# 03_Beam_Inputs.net
KiCad netlist of a schematic drawn in Altium Designer
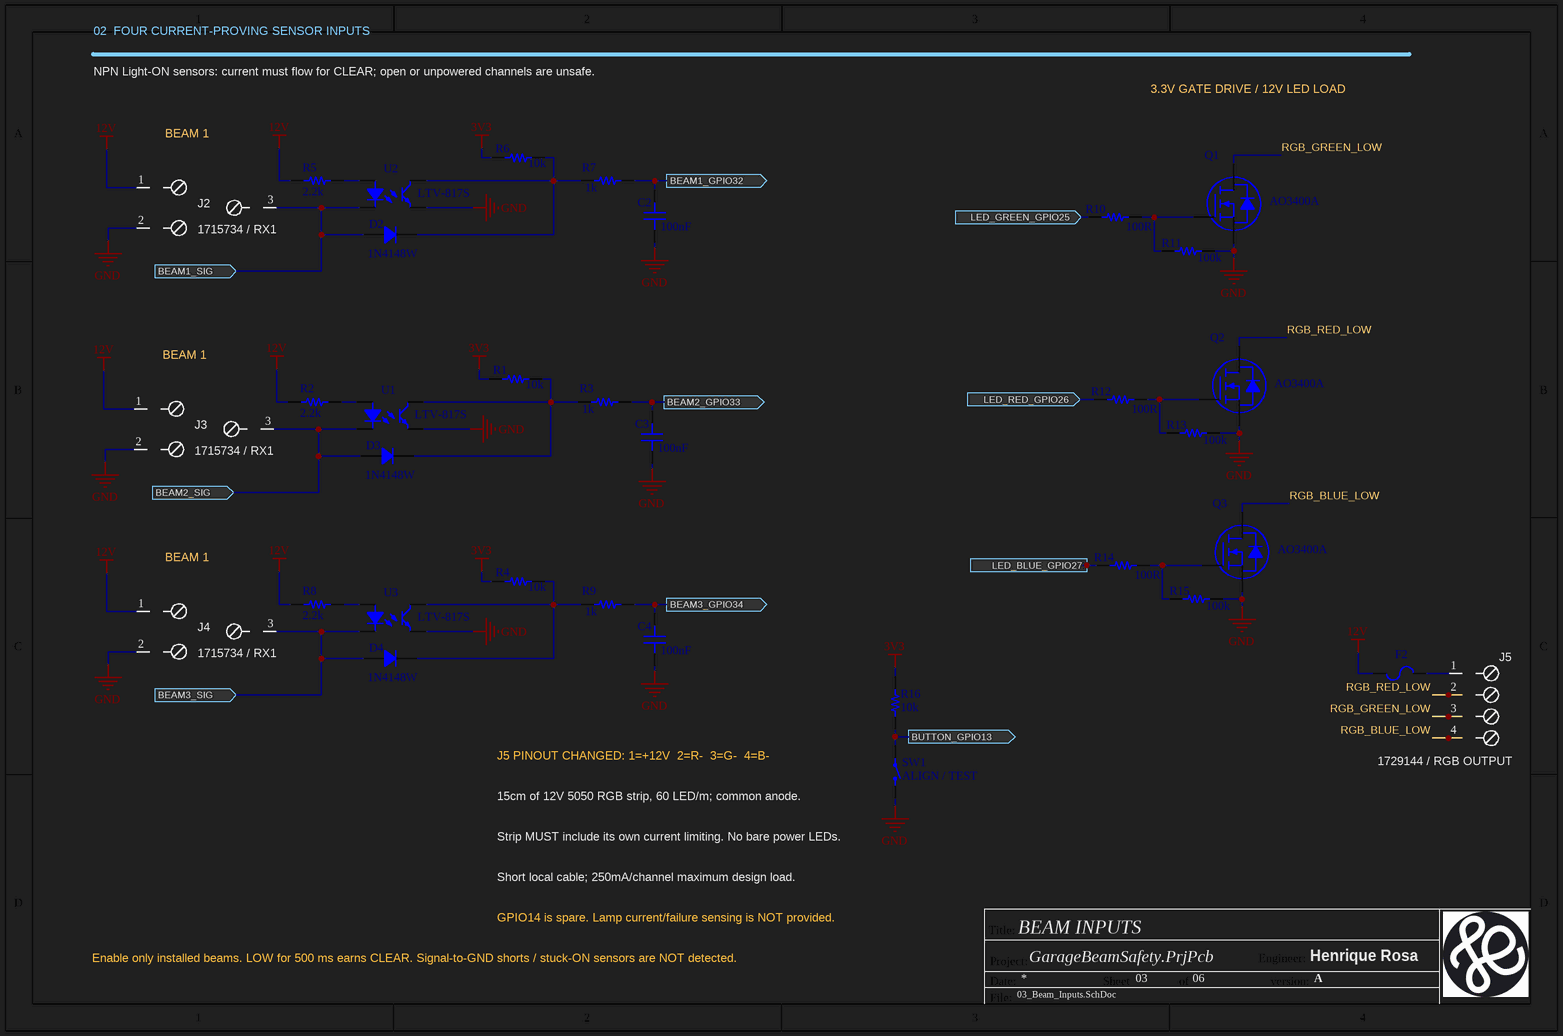
[diagram p0: 03_Beam_Inputs.SchDoc]

(export (version "E")
  (design (tool "Eeschema 10.0.6"))
  (components
    (comp (ref "C2")
      (value "100nF")
      (footprint "PCB - CAPACITOR - MLCC - MURATA GRM21B 0805_2012:MURATA GRM21B 0805_2012")
      (description "SMT Capacitor")
      (fields (field (name "PART NUMBER") "GRM21BR71H104KA01L") (field (name "MANUFACTURER") "Murata"))
      (libsource (lib "SCH - PASSIVES - CAPACITOR") (part "Capacitor"))
    )
    (comp (ref "C3")
      (value "100nF")
      (footprint "PCB - CAPACITOR - MLCC - MURATA GRM21B 0805_2012:MURATA GRM21B 0805_2012")
      (description "SMT Capacitor")
      (fields (field (name "PART NUMBER") "GRM21BR71H104KA01L") (field (name "MANUFACTURER") "Murata"))
      (libsource (lib "SCH - PASSIVES - CAPACITOR") (part "Capacitor"))
    )
    (comp (ref "C4")
      (value "100nF")
      (footprint "PCB - CAPACITOR - MLCC - MURATA GRM21B 0805_2012:MURATA GRM21B 0805_2012")
      (description "SMT Capacitor")
      (fields (field (name "PART NUMBER") "GRM21BR71H104KA01L") (field (name "MANUFACTURER") "Murata"))
      (libsource (lib "SCH - PASSIVES - CAPACITOR") (part "Capacitor"))
    )
    (comp (ref "D2")
      (value "1N4148W")
      (footprint "PinRepairFootprints:1N4148W_SOD123_A1_K2")
      (description "Rectifier Diode")
      (fields (field (name "MANUFACTURER") "Nexperia"))
      (libsource (lib "SCH - DIODES - DIODE") (part "Diode"))
    )
    (comp (ref "D3")
      (value "1N4148W")
      (footprint "PinRepairFootprints:1N4148W_SOD123_A1_K2")
      (description "Rectifier Diode")
      (fields (field (name "MANUFACTURER") "Nexperia"))
      (libsource (lib "SCH - DIODES - DIODE") (part "Diode"))
    )
    (comp (ref "D4")
      (value "1N4148W")
      (footprint "PinRepairFootprints:1N4148W_SOD123_A1_K2")
      (description "Rectifier Diode")
      (fields (field (name "MANUFACTURER") "Nexperia"))
      (libsource (lib "SCH - DIODES - DIODE") (part "Diode"))
    )
    (comp (ref "F2")
      (value "0.5A FAST")
      (footprint "PinRepairFootprints:LITTELFUSE_0451_2410")
      (description "GENERIC_fuse")
      (fields
        (field (name "MANUFACTURER") "Littelfuse")
        (field (name "MANUFACTURER PART NUMBER") "0451.500MRL")
      )
      (libsource (lib "SCH - FUSE - MOUNTED FUSE") (part "MOUNTED FUSE"))
    )
    (comp (ref "J2")
      (value "1715734 / RX1")
      (footprint "OpticalHardware:PHOENIX_1715734_MKDS_3_508")
      (description "12V / GND / NPN signal terminal")
      (fields
        (field (name "MANUFACTURER") "Phoenix Contact")
        (field (name "MANUFACTURER PART NUMBER") "1715734")
      )
      (libsource (lib "ReviewedComponents_20260912-233454") (part "1715734__J2_view"))
    )
    (comp (ref "J3")
      (value "1715734 / RX1")
      (footprint "OpticalHardware:PHOENIX_1715734_MKDS_3_508")
      (description "12V / GND / NPN signal terminal")
      (fields
        (field (name "MANUFACTURER") "Phoenix Contact")
        (field (name "MANUFACTURER PART NUMBER") "1715734")
      )
      (libsource (lib "ReviewedComponents_20260912-233454") (part "1715734__J2_view"))
    )
    (comp (ref "J4")
      (value "1715734 / RX1")
      (footprint "OpticalHardware:PHOENIX_1715734_MKDS_3_508")
      (description "12V / GND / NPN signal terminal")
      (fields
        (field (name "MANUFACTURER") "Phoenix Contact")
        (field (name "MANUFACTURER PART NUMBER") "1715734")
      )
      (libsource (lib "ReviewedComponents_20260912-233454") (part "1715734__J2_view"))
    )
    (comp (ref "J5")
      (value "1729144 / RGB OUTPUT")
      (footprint "PartSpecificFootprints:PHOENIX_1729144_MKDSN_4_508")
      (description "Common-anode analogue RGB strip; NOT addressable")
      (fields
        (field (name "MANUFACTURER") "Phoenix Contact")
        (field (name "MANUFACTURER PART NUMBER") "1729144")
      )
      (libsource (lib "ReviewedComponents_20260912-233454") (part "1729144__J5_view"))
    )
    (comp (ref "Q1")
      (value "AO3400A")
      (footprint "PinRepairFootprints:AO3400A_G1_S2_D3")
      (fields (field (name "MANUFACTURER") "Alpha and Omega Semiconductor"))
      (libsource (lib "SCH - FET - N-CH - MOSFET SINGLE GDS") (part "MOSFET SINGLE GDS"))
    )
    (comp (ref "Q2")
      (value "AO3400A")
      (footprint "PinRepairFootprints:AO3400A_G1_S2_D3")
      (fields (field (name "MANUFACTURER") "Alpha and Omega Semiconductor"))
      (libsource (lib "SCH - FET - N-CH - MOSFET SINGLE GDS") (part "MOSFET SINGLE GDS"))
    )
    (comp (ref "Q3")
      (value "AO3400A")
      (footprint "PinRepairFootprints:AO3400A_G1_S2_D3")
      (fields (field (name "MANUFACTURER") "Alpha and Omega Semiconductor"))
      (libsource (lib "SCH - FET - N-CH - MOSFET SINGLE GDS") (part "MOSFET SINGLE GDS"))
    )
    (comp (ref "R1")
      (value "10k")
      (footprint "PCB - RESISTOR - CHIP - YAGEO RES 0805_2012:YAGEO RES 0805_2012")
      (description "SMT Resistor")
      (fields (field (name "PART NUMBER") "RC0805FR-0710KL") (field (name "MANUFACTURER") "Yageo"))
      (libsource (lib "SCH - PASSIVES - RESISTOR") (part "Resistor"))
    )
    (comp (ref "R2")
      (value "2.2k")
      (footprint "PCB - RESISTOR - CHIP - YAGEO RES 0805_2012:YAGEO RES 0805_2012")
      (description "SMT Resistor")
      (fields (field (name "PART NUMBER") "RC0805FR-072K2L") (field (name "MANUFACTURER") "Yageo"))
      (libsource (lib "SCH - PASSIVES - RESISTOR") (part "Resistor"))
    )
    (comp (ref "R3")
      (value "1k")
      (footprint "PCB - RESISTOR - CHIP - YAGEO RES 0805_2012:YAGEO RES 0805_2012")
      (description "SMT Resistor")
      (fields (field (name "PART NUMBER") "RC0805FR-071KL") (field (name "MANUFACTURER") "Yageo"))
      (libsource (lib "SCH - PASSIVES - RESISTOR") (part "Resistor"))
    )
    (comp (ref "R4")
      (value "10k")
      (footprint "PCB - RESISTOR - CHIP - YAGEO RES 0805_2012:YAGEO RES 0805_2012")
      (description "SMT Resistor")
      (fields (field (name "PART NUMBER") "RC0805FR-0710KL") (field (name "MANUFACTURER") "Yageo"))
      (libsource (lib "SCH - PASSIVES - RESISTOR") (part "Resistor"))
    )
    (comp (ref "R5")
      (value "2.2k")
      (footprint "PCB - RESISTOR - CHIP - YAGEO RES 0805_2012:YAGEO RES 0805_2012")
      (description "SMT Resistor")
      (fields (field (name "PART NUMBER") "RC0805FR-072K2L") (field (name "MANUFACTURER") "Yageo"))
      (libsource (lib "SCH - PASSIVES - RESISTOR") (part "Resistor"))
    )
    (comp (ref "R6")
      (value "10k")
      (footprint "PCB - RESISTOR - CHIP - YAGEO RES 0805_2012:YAGEO RES 0805_2012")
      (description "SMT Resistor")
      (fields (field (name "PART NUMBER") "RC0805FR-0710KL") (field (name "MANUFACTURER") "Yageo"))
      (libsource (lib "SCH - PASSIVES - RESISTOR") (part "Resistor"))
    )
    (comp (ref "R7")
      (value "1k")
      (footprint "PCB - RESISTOR - CHIP - YAGEO RES 0805_2012:YAGEO RES 0805_2012")
      (description "SMT Resistor")
      (fields (field (name "PART NUMBER") "RC0805FR-071KL") (field (name "MANUFACTURER") "Yageo"))
      (libsource (lib "SCH - PASSIVES - RESISTOR") (part "Resistor"))
    )
    (comp (ref "R8")
      (value "2.2k")
      (footprint "PCB - RESISTOR - CHIP - YAGEO RES 0805_2012:YAGEO RES 0805_2012")
      (description "SMT Resistor")
      (fields (field (name "PART NUMBER") "RC0805FR-072K2L") (field (name "MANUFACTURER") "Yageo"))
      (libsource (lib "SCH - PASSIVES - RESISTOR") (part "Resistor"))
    )
    (comp (ref "R9")
      (value "1k")
      (footprint "PCB - RESISTOR - CHIP - YAGEO RES 0805_2012:YAGEO RES 0805_2012")
      (description "SMT Resistor")
      (fields (field (name "PART NUMBER") "RC0805FR-071KL") (field (name "MANUFACTURER") "Yageo"))
      (libsource (lib "SCH - PASSIVES - RESISTOR") (part "Resistor"))
    )
    (comp (ref "R10")
      (value "100R")
      (footprint "PCB - RESISTOR - CHIP - YAGEO RES 0805_2012:YAGEO RES 0805_2012")
      (description "SMT Resistor")
      (fields (field (name "PART NUMBER") "RC0805FR-07100RL") (field (name "MANUFACTURER") "Yageo"))
      (libsource (lib "SCH - PASSIVES - RESISTOR") (part "Resistor"))
    )
    (comp (ref "R11")
      (value "100k")
      (footprint "PCB - RESISTOR - CHIP - YAGEO RES 0805_2012:YAGEO RES 0805_2012")
      (description "SMT Resistor")
      (fields (field (name "PART NUMBER") "RC0805FR-07100KL") (field (name "MANUFACTURER") "Yageo"))
      (libsource (lib "SCH - PASSIVES - RESISTOR") (part "Resistor"))
    )
    (comp (ref "R12")
      (value "100R")
      (footprint "PCB - RESISTOR - CHIP - YAGEO RES 0805_2012:YAGEO RES 0805_2012")
      (description "SMT Resistor")
      (fields (field (name "PART NUMBER") "RC0805FR-07100RL") (field (name "MANUFACTURER") "Yageo"))
      (libsource (lib "SCH - PASSIVES - RESISTOR") (part "Resistor"))
    )
    (comp (ref "R13")
      (value "100k")
      (footprint "PCB - RESISTOR - CHIP - YAGEO RES 0805_2012:YAGEO RES 0805_2012")
      (description "SMT Resistor")
      (fields (field (name "PART NUMBER") "RC0805FR-07100KL") (field (name "MANUFACTURER") "Yageo"))
      (libsource (lib "SCH - PASSIVES - RESISTOR") (part "Resistor"))
    )
    (comp (ref "R14")
      (value "100R")
      (footprint "PCB - RESISTOR - CHIP - YAGEO RES 0805_2012:YAGEO RES 0805_2012")
      (description "SMT Resistor")
      (fields (field (name "PART NUMBER") "RC0805FR-07100RL") (field (name "MANUFACTURER") "Yageo"))
      (libsource (lib "SCH - PASSIVES - RESISTOR") (part "Resistor"))
    )
    (comp (ref "R15")
      (value "100k")
      (footprint "PCB - RESISTOR - CHIP - YAGEO RES 0805_2012:YAGEO RES 0805_2012")
      (description "SMT Resistor")
      (fields (field (name "PART NUMBER") "RC0805FR-07100KL") (field (name "MANUFACTURER") "Yageo"))
      (libsource (lib "SCH - PASSIVES - RESISTOR") (part "Resistor"))
    )
    (comp (ref "R16")
      (value "10k")
      (footprint "PCB - RESISTOR - CHIP - YAGEO RES 0805_2012:YAGEO RES 0805_2012")
      (description "SMT Resistor")
      (fields (field (name "PART NUMBER") "RC0805FR-0710KL") (field (name "MANUFACTURER") "Yageo"))
      (libsource (lib "SCH - PASSIVES - RESISTOR") (part "Resistor"))
    )
    (comp (ref "SW1")
      (value "ALIGN / TEST")
      (footprint "PinRepairFootprints:OMRON_B3FS1000P_LOGICAL_1_2")
      (fields (field (name "MANUFACTURER") "Omron") (field (name "MANUFACTURER PART NUMBER") "B3FS-1000P"))
      (libsource (lib "SCH - SWITCH - SPST 2PIN") (part "SPST 2PIN"))
    )
    (comp (ref "U1")
      (value "LTV-817S")
      (footprint "PCB - OPTOISOLATOR - LITEON LTV-817:LITEON LTV-817")
      (fields
        (field (name "MANUFACTURER") "Lite-On")
        (field (name "MANUFACTURER PART NUMBER") "LTV-817S-TA1")
      )
      (libsource (lib "SCH - OPTOISOLATORS - OPTOISOLATOR") (part "Optoisolator"))
    )
    (comp (ref "U2")
      (value "LTV-817S")
      (footprint "PCB - OPTOISOLATOR - LITEON LTV-817:LITEON LTV-817")
      (fields
        (field (name "MANUFACTURER") "Lite-On")
        (field (name "MANUFACTURER PART NUMBER") "LTV-817S-TA1")
      )
      (libsource (lib "SCH - OPTOISOLATORS - OPTOISOLATOR") (part "Optoisolator"))
    )
    (comp (ref "U3")
      (value "LTV-817S")
      (footprint "PCB - OPTOISOLATOR - LITEON LTV-817:LITEON LTV-817")
      (fields
        (field (name "MANUFACTURER") "Lite-On")
        (field (name "MANUFACTURER PART NUMBER") "LTV-817S-TA1")
      )
      (libsource (lib "SCH - OPTOISOLATORS - OPTOISOLATOR") (part "Optoisolator"))
    )
  )
  (nets
    (net (code "1") (name "/BEAM1_GPIO32") (class "Default")
      (node (ref "C2") (pin "2") (pinfunction "2_2") (pintype "passive"))
      (node (ref "R7") (pin "2") (pinfunction "2_2") (pintype "passive"))
    )
    (net (code "2") (name "/BEAM1_SIG") (class "Default")
      (node (ref "D2") (pin "1") (pinfunction "1_1") (pintype "passive"))
      (node (ref "J2") (pin "3") (pinfunction "OUT_3") (pintype "passive"))
      (node (ref "U2") (pin "2") (pinfunction "2_2") (pintype "passive"))
    )
    (net (code "3") (name "/BEAM2_GPIO33") (class "Default")
      (node (ref "C3") (pin "2") (pinfunction "2_2") (pintype "passive"))
      (node (ref "R3") (pin "2") (pinfunction "2_2") (pintype "passive"))
    )
    (net (code "4") (name "/BEAM2_SIG") (class "Default")
      (node (ref "D3") (pin "1") (pinfunction "1_1") (pintype "passive"))
      (node (ref "J3") (pin "3") (pinfunction "OUT_3") (pintype "passive"))
      (node (ref "U1") (pin "2") (pinfunction "2_2") (pintype "passive"))
    )
    (net (code "5") (name "/BEAM3_GPIO34") (class "Default")
      (node (ref "C4") (pin "2") (pinfunction "2_2") (pintype "passive"))
      (node (ref "R9") (pin "2") (pinfunction "2_2") (pintype "passive"))
    )
    (net (code "6") (name "/BEAM3_SIG") (class "Default")
      (node (ref "D4") (pin "1") (pinfunction "1_1") (pintype "passive"))
      (node (ref "J4") (pin "3") (pinfunction "OUT_3") (pintype "passive"))
      (node (ref "U3") (pin "2") (pinfunction "2_2") (pintype "passive"))
    )
    (net (code "7") (name "/BUTTON_GPIO13") (class "Default")
      (node (ref "R16") (pin "2") (pinfunction "2_2") (pintype "passive"))
      (node (ref "SW1") (pin "1") (pinfunction "1_1") (pintype "passive"))
    )
    (net (code "8") (name "/LED_BLUE_GPIO27") (class "Default")
      (node (ref "R14") (pin "1") (pinfunction "1_1") (pintype "passive"))
    )
    (net (code "9") (name "/LED_GREEN_GPIO25") (class "Default")
      (node (ref "R10") (pin "1") (pinfunction "1_1") (pintype "passive"))
    )
    (net (code "10") (name "/LED_RED_GPIO26") (class "Default")
      (node (ref "R12") (pin "1") (pinfunction "1_1") (pintype "passive"))
    )
    (net (code "11") (name "/RGB_BLUE_LOW") (class "Default")
      (node (ref "J5") (pin "4") (pinfunction "B-_4") (pintype "passive"))
      (node (ref "Q3") (pin "3") (pinfunction "D_3") (pintype "passive"))
    )
    (net (code "12") (name "/RGB_GREEN_LOW") (class "Default")
      (node (ref "J5") (pin "3") (pinfunction "G-_3") (pintype "passive"))
      (node (ref "Q1") (pin "3") (pinfunction "D_3") (pintype "passive"))
    )
    (net (code "13") (name "/RGB_RED_LOW") (class "Default")
      (node (ref "J5") (pin "2") (pinfunction "R-_2") (pintype "passive"))
      (node (ref "Q2") (pin "3") (pinfunction "D_3") (pintype "passive"))
    )
    (net (code "14") (name "3V3") (class "Default")
      (node (ref "R1") (pin "1") (pinfunction "1_1") (pintype "passive"))
      (node (ref "R16") (pin "1") (pinfunction "1_1") (pintype "passive"))
      (node (ref "R4") (pin "1") (pinfunction "1_1") (pintype "passive"))
      (node (ref "R6") (pin "1") (pinfunction "1_1") (pintype "passive"))
    )
    (net (code "15") (name "12V") (class "Default")
      (node (ref "F2") (pin "1") (pintype "passive"))
      (node (ref "J2") (pin "1") (pinfunction "+12V_1") (pintype "passive"))
      (node (ref "J3") (pin "1") (pinfunction "+12V_1") (pintype "passive"))
      (node (ref "J4") (pin "1") (pinfunction "+12V_1") (pintype "passive"))
      (node (ref "R2") (pin "1") (pinfunction "1_1") (pintype "passive"))
      (node (ref "R5") (pin "1") (pinfunction "1_1") (pintype "passive"))
      (node (ref "R8") (pin "1") (pinfunction "1_1") (pintype "passive"))
    )
    (net (code "16") (name "GND") (class "Default")
      (node (ref "C2") (pin "1") (pinfunction "1_1") (pintype "passive"))
      (node (ref "C3") (pin "1") (pinfunction "1_1") (pintype "passive"))
      (node (ref "C4") (pin "1") (pinfunction "1_1") (pintype "passive"))
      (node (ref "J2") (pin "2") (pinfunction "0V_2") (pintype "passive"))
      (node (ref "J3") (pin "2") (pinfunction "0V_2") (pintype "passive"))
      (node (ref "J4") (pin "2") (pinfunction "0V_2") (pintype "passive"))
      (node (ref "Q1") (pin "2") (pinfunction "S_2") (pintype "passive"))
      (node (ref "Q2") (pin "2") (pinfunction "S_2") (pintype "passive"))
      (node (ref "Q3") (pin "2") (pinfunction "S_2") (pintype "passive"))
      (node (ref "R11") (pin "2") (pinfunction "2_2") (pintype "passive"))
      (node (ref "R13") (pin "2") (pinfunction "2_2") (pintype "passive"))
      (node (ref "R15") (pin "2") (pinfunction "2_2") (pintype "passive"))
      (node (ref "SW1") (pin "2") (pinfunction "2_2") (pintype "passive"))
      (node (ref "U1") (pin "3") (pinfunction "3_3") (pintype "passive"))
      (node (ref "U2") (pin "3") (pinfunction "3_3") (pintype "passive"))
      (node (ref "U3") (pin "3") (pinfunction "3_3") (pintype "passive"))
    )
    (net (code "17") (name "Net-(D2-Pad2)") (class "Default")
      (node (ref "D2") (pin "2") (pinfunction "2_2") (pintype "passive"))
      (node (ref "R6") (pin "2") (pinfunction "2_2") (pintype "passive"))
      (node (ref "R7") (pin "1") (pinfunction "1_1") (pintype "passive"))
      (node (ref "U2") (pin "4") (pinfunction "4_4") (pintype "passive"))
    )
    (net (code "18") (name "Net-(D3-Pad2)") (class "Default")
      (node (ref "D3") (pin "2") (pinfunction "2_2") (pintype "passive"))
      (node (ref "R1") (pin "2") (pinfunction "2_2") (pintype "passive"))
      (node (ref "R3") (pin "1") (pinfunction "1_1") (pintype "passive"))
      (node (ref "U1") (pin "4") (pinfunction "4_4") (pintype "passive"))
    )
    (net (code "19") (name "Net-(D4-Pad2)") (class "Default")
      (node (ref "D4") (pin "2") (pinfunction "2_2") (pintype "passive"))
      (node (ref "R4") (pin "2") (pinfunction "2_2") (pintype "passive"))
      (node (ref "R9") (pin "1") (pinfunction "1_1") (pintype "passive"))
      (node (ref "U3") (pin "4") (pinfunction "4_4") (pintype "passive"))
    )
    (net (code "20") (name "Net-(J5-+12V)") (class "Default")
      (node (ref "F2") (pin "2") (pintype "passive"))
      (node (ref "J5") (pin "1") (pinfunction "+12V_1") (pintype "power_in"))
    )
    (net (code "21") (name "Net-(Q1-G)") (class "Default")
      (node (ref "Q1") (pin "1") (pinfunction "G_1") (pintype "passive"))
      (node (ref "R10") (pin "2") (pinfunction "2_2") (pintype "passive"))
      (node (ref "R11") (pin "1") (pinfunction "1_1") (pintype "passive"))
    )
    (net (code "22") (name "Net-(Q2-G)") (class "Default")
      (node (ref "Q2") (pin "1") (pinfunction "G_1") (pintype "passive"))
      (node (ref "R12") (pin "2") (pinfunction "2_2") (pintype "passive"))
      (node (ref "R13") (pin "1") (pinfunction "1_1") (pintype "passive"))
    )
    (net (code "23") (name "Net-(Q3-G)") (class "Default")
      (node (ref "Q3") (pin "1") (pinfunction "G_1") (pintype "passive"))
      (node (ref "R14") (pin "2") (pinfunction "2_2") (pintype "passive"))
      (node (ref "R15") (pin "1") (pinfunction "1_1") (pintype "passive"))
    )
    (net (code "24") (name "Net-(R2-Pad2)") (class "Default")
      (node (ref "R2") (pin "2") (pinfunction "2_2") (pintype "passive"))
      (node (ref "U1") (pin "1") (pinfunction "1_1") (pintype "passive"))
    )
    (net (code "25") (name "Net-(R5-Pad2)") (class "Default")
      (node (ref "R5") (pin "2") (pinfunction "2_2") (pintype "passive"))
      (node (ref "U2") (pin "1") (pinfunction "1_1") (pintype "passive"))
    )
    (net (code "26") (name "Net-(R8-Pad2)") (class "Default")
      (node (ref "R8") (pin "2") (pinfunction "2_2") (pintype "passive"))
      (node (ref "U3") (pin "1") (pinfunction "1_1") (pintype "passive"))
    )
  )
)
